# Cup_and_Wash_v2_relay.net
KiCad netlist of a schematic drawn in EAGLE
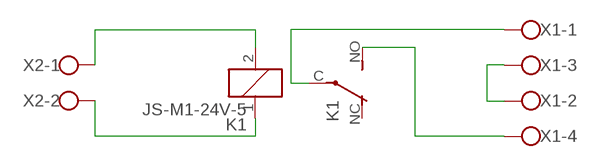
[diagram p0: schematic, sheet 1]

(export (version "E")
  (design (tool "Eeschema 10.0.6"))
  (components
    (comp (ref "K1")
      (value "JS-M1-24V-5")
      (footprint "eagle-import:JS-M")
      (fields (field (name "MF") "FARNELL") (field (name "MPN") "JSM1-12V-5"))
      (libsource (lib "eagle-import") (part "JS-M1-12V-5"))
    )
    (comp (ref "X1")
      (value "W237-4")
      (footprint "eagle-import:W237-4")
      (libsource (lib "eagle-import") (part "W237-4"))
    )
    (comp (ref "X2")
      (value "W237-102")
      (footprint "eagle-import:W237-102")
      (fields (field (name "MPN") "237-102"))
      (libsource (lib "eagle-import") (part "W237-102"))
    )
  )
  (nets
    (net (code "1") (name "Net-(K1B-P)") (class "Default")
      (node (ref "K1") (pin "C") (pinfunction "P_C") (pintype "passive"))
      (node (ref "X1") (pin "1") (pinfunction "KL_1") (pintype "passive"))
    )
    (net (code "2") (name "Net-(K1B-S)") (class "Default")
      (node (ref "K1") (pin "NO") (pinfunction "S_NO") (pintype "passive"))
      (node (ref "X1") (pin "4") (pinfunction "KL_4") (pintype "passive"))
    )
    (net (code "3") (name "Net-(X1B-KL)") (class "Default")
      (node (ref "X1") (pin "2") (pinfunction "KL_2") (pintype "passive"))
      (node (ref "X1") (pin "3") (pinfunction "KL_3") (pintype "passive"))
    )
    (net (code "4") (name "Net-(X2A-KL)") (class "Default")
      (node (ref "K1") (pin "2") (pinfunction "2_2") (pintype "passive"))
      (node (ref "X2") (pin "1") (pinfunction "KL_1") (pintype "passive"))
    )
    (net (code "5") (name "Net-(X2B-KL)") (class "Default")
      (node (ref "K1") (pin "1") (pinfunction "1_1") (pintype "passive"))
      (node (ref "X2") (pin "2") (pinfunction "KL_2") (pintype "passive"))
    )
    (net (code "6") (name "unconnected-(K1B-O-PadNC)") (class "Default")
      (node (ref "K1") (pin "NC") (pinfunction "O_NC") (pintype "passive"))
    )
  )
)
